# I2C_MUX.net
KiCad netlist of a schematic drawn in Altium Designer
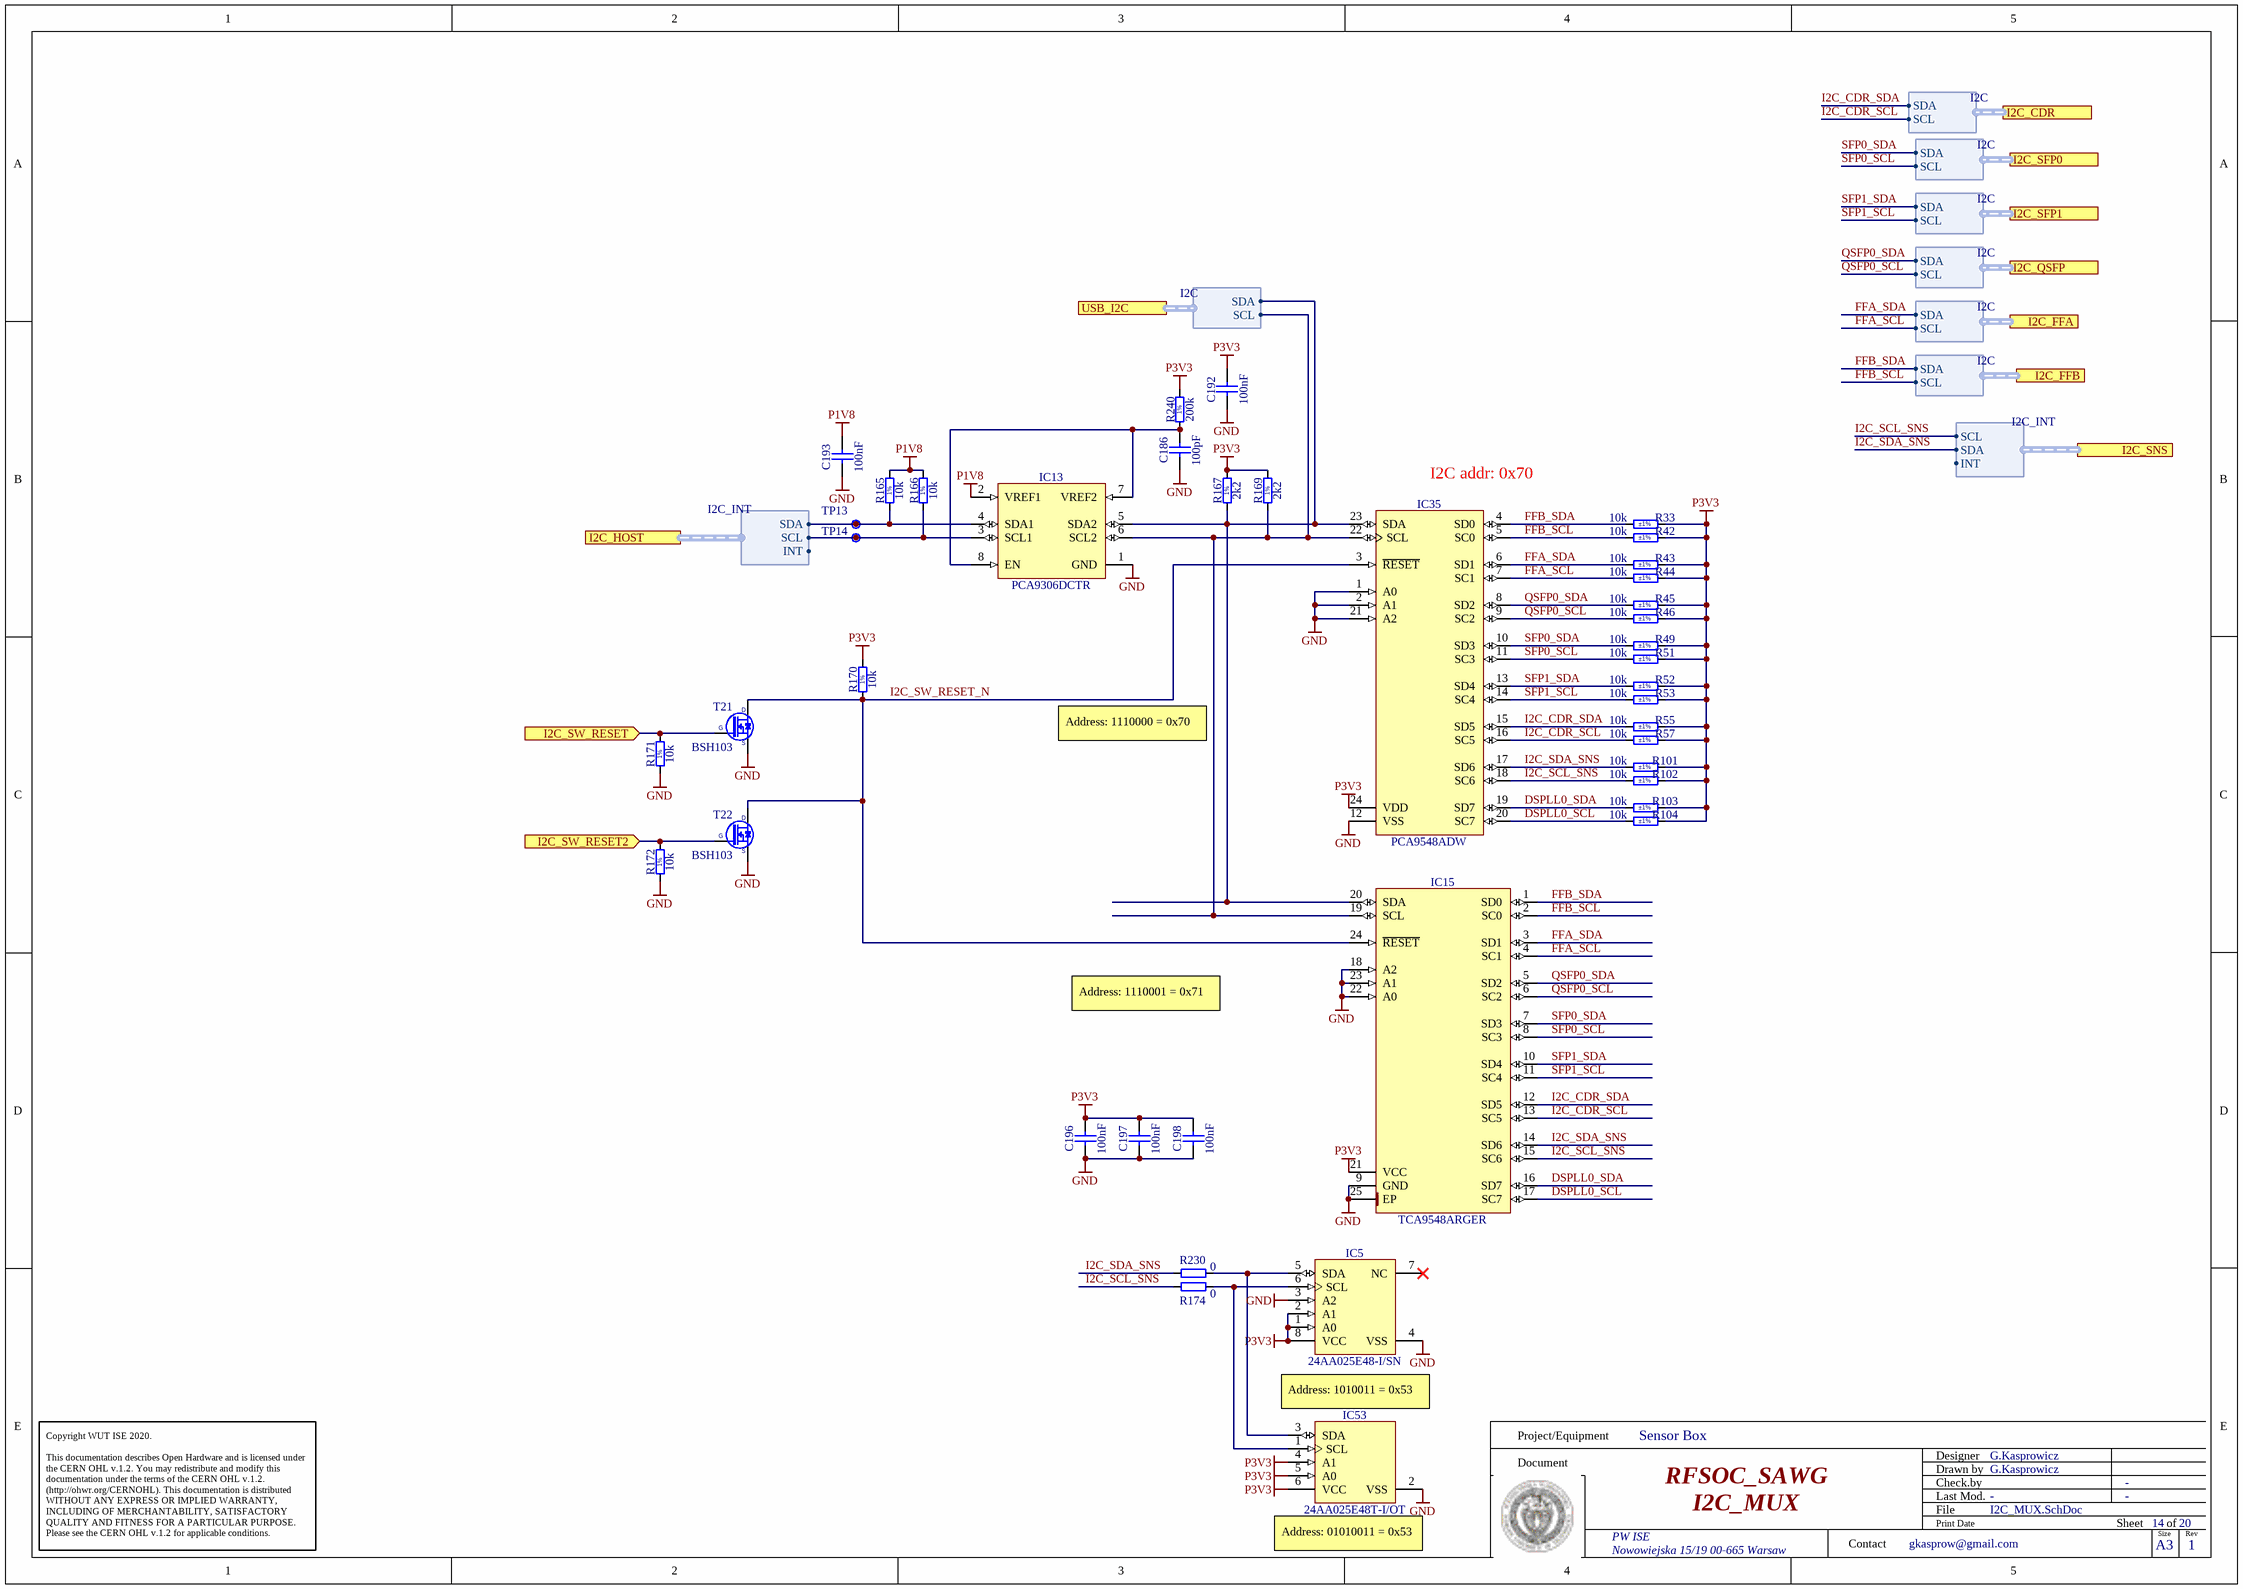
[diagram p0: I2C_MUX.SchDoc]

(export (version "E")
  (design (tool "Eeschema 10.0.6"))
  (components
    (comp (ref "C186")
      (value "100pF")
      (footprint "CAPC1005X55N")
      (description "Non-polarised capacitor")
      (fields
        (field (name "PART NUMBER") "CC0402_100PF_50V_5%_C0G")
        (field (name "VOLTAGE") "50V")
        (field (name "AUTHOR") "CERN DEM JLC")
      )
      (libsource (lib "Capacitors") (part "Capacitor - non polarized"))
    )
    (comp (ref "C192")
      (value "100nF")
      (footprint "CAPC1005X55N")
      (description "Non-polarised capacitor")
      (fields
        (field (name "PART NUMBER") "CC0402_100NF_16V_10%_X7R")
        (field (name "VOLTAGE") "16V")
        (field (name "AUTHOR") "CERN DEM JLC")
      )
      (libsource (lib "Capacitors") (part "Capacitor - non polarized"))
    )
    (comp (ref "C193")
      (value "100nF")
      (footprint "CAPC1005X55N")
      (description "Non-polarised capacitor")
      (fields
        (field (name "PART NUMBER") "CC0402_100NF_16V_10%_X7R")
        (field (name "VOLTAGE") "16V")
        (field (name "AUTHOR") "CERN DEM JLC")
      )
      (libsource (lib "Capacitors") (part "Capacitor - non polarized"))
    )
    (comp (ref "C196")
      (value "100nF")
      (footprint "CAPC1005X55N")
      (description "Non-polarised capacitor")
      (fields
        (field (name "PART NUMBER") "CC0402_100NF_16V_10%_X7R")
        (field (name "VOLTAGE") "16V")
        (field (name "AUTHOR") "CERN DEM JLC")
      )
      (libsource (lib "Capacitors") (part "Capacitor - non polarized"))
    )
    (comp (ref "C197")
      (value "100nF")
      (footprint "CAPC1005X55N")
      (description "Non-polarised capacitor")
      (fields
        (field (name "PART NUMBER") "CC0402_100NF_16V_10%_X7R")
        (field (name "VOLTAGE") "16V")
        (field (name "AUTHOR") "CERN DEM JLC")
      )
      (libsource (lib "Capacitors") (part "Capacitor - non polarized"))
    )
    (comp (ref "C198")
      (value "100nF")
      (footprint "CAPC1005X55N")
      (description "Non-polarised capacitor")
      (fields
        (field (name "PART NUMBER") "CC0402_100NF_16V_10%_X7R")
        (field (name "VOLTAGE") "16V")
        (field (name "AUTHOR") "CERN DEM JLC")
      )
      (libsource (lib "Capacitors") (part "Capacitor - non polarized"))
    )
    (comp (ref "IC5")
      (value "24AA025E48-I/SN")
      (footprint "SOIC127P600X175-8N")
      (description "1.7V-5.5V, 2K I2C™ Serial EEPROMs with EUI-48™ Node Identity")
      (fields (field (name "MANUFACTURER") "MICROCHIP TECHNOLOGY") (field (name "AUTHOR") "CERN DEM MR"))
      (libsource (lib "ICs And Semiconductors") (part "24AA025E48-I/SN"))
    )
    (comp (ref "IC13")
      (value "PCA9306DCTR")
      (footprint "SOP65P400X130-8N")
      (description "Dual Bidirectional I2C Bus And SMBus Voltage-Level Translator")
      (fields (field (name "MANUFACTURER") "TEXAS INSTRUMENTS") (field (name "AUTHOR") "CERN DEM JLC"))
      (libsource (lib "ICs And Semiconductors") (part "PCA9306D"))
    )
    (comp (ref "IC15")
      (value "TCA9548ARGER")
      (footprint "QFN50P400X400X100-25N-S220")
      (description "Low Voltage 8-Channel I2C Switch With Reset")
      (fields (field (name "MANUFACTURER") "TEXAS INSTRUMENTS") (field (name "AUTHOR") "CERN DEM JLC"))
      (libsource (lib "ICs And Semiconductors") (part "TCA9548ARGER"))
    )
    (comp (ref "IC35")
      (value "PCA9548ADW")
      (footprint "SOIC127P1030X265-24N")
      (description "8-Channel I2C-Bus Switch with Reset")
      (fields (field (name "MANUFACTURER") "TEXAS INSTRUMENTS") (field (name "AUTHOR") "CERN DEM JLC"))
      (libsource (lib "ICs And Semiconductors") (part "PCA9548ADW"))
    )
    (comp (ref "IC53")
      (value "24AA025E48T-I/OT")
      (footprint "SOT95P280X145-6N")
      (description "1.7V-5.5V, 2K I2C Serial EEPROM With EUI-48 Node Identity")
      (fields (field (name "MANUFACTURER") "MICROCHIP TECHNOLOGY") (field (name "AUTHOR") "CERN DEM BC"))
      (libsource (lib "ICs And Semiconductors") (part "24AA025E48T-I/OT"))
    )
    (comp (ref "R33")
      (value "10k")
      (footprint "RESC1005X40N")
      (description "Resistor - 1%")
      (fields
        (field (name "TOLERANCE") "±1%")
        (field (name "PART NUMBER") "R0402_10K_1%_0.0625W_100PPM")
        (field (name "POWER") "0.0625W")
        (field (name "AUTHOR") "CERN DEM JLC")
      )
      (libsource (lib "Resistors") (part "Resistor - 1%"))
    )
    (comp (ref "R42")
      (value "10k")
      (footprint "RESC1005X40N")
      (description "Resistor - 1%")
      (fields
        (field (name "TOLERANCE") "±1%")
        (field (name "PART NUMBER") "R0402_10K_1%_0.0625W_100PPM")
        (field (name "POWER") "0.0625W")
        (field (name "AUTHOR") "CERN DEM JLC")
      )
      (libsource (lib "Resistors") (part "Resistor - 1%"))
    )
    (comp (ref "R43")
      (value "10k")
      (footprint "RESC1005X40N")
      (description "Resistor - 1%")
      (fields
        (field (name "TOLERANCE") "±1%")
        (field (name "PART NUMBER") "R0402_10K_1%_0.0625W_100PPM")
        (field (name "POWER") "0.0625W")
        (field (name "AUTHOR") "CERN DEM JLC")
      )
      (libsource (lib "Resistors") (part "Resistor - 1%"))
    )
    (comp (ref "R44")
      (value "10k")
      (footprint "RESC1005X40N")
      (description "Resistor - 1%")
      (fields
        (field (name "TOLERANCE") "±1%")
        (field (name "PART NUMBER") "R0402_10K_1%_0.0625W_100PPM")
        (field (name "POWER") "0.0625W")
        (field (name "AUTHOR") "CERN DEM JLC")
      )
      (libsource (lib "Resistors") (part "Resistor - 1%"))
    )
    (comp (ref "R45")
      (value "10k")
      (footprint "RESC1005X40N")
      (description "Resistor - 1%")
      (fields
        (field (name "TOLERANCE") "±1%")
        (field (name "PART NUMBER") "R0402_10K_1%_0.0625W_100PPM")
        (field (name "POWER") "0.0625W")
        (field (name "AUTHOR") "CERN DEM JLC")
      )
      (libsource (lib "Resistors") (part "Resistor - 1%"))
    )
    (comp (ref "R46")
      (value "10k")
      (footprint "RESC1005X40N")
      (description "Resistor - 1%")
      (fields
        (field (name "TOLERANCE") "±1%")
        (field (name "PART NUMBER") "R0402_10K_1%_0.0625W_100PPM")
        (field (name "POWER") "0.0625W")
        (field (name "AUTHOR") "CERN DEM JLC")
      )
      (libsource (lib "Resistors") (part "Resistor - 1%"))
    )
    (comp (ref "R49")
      (value "10k")
      (footprint "RESC1005X40N")
      (description "Resistor - 1%")
      (fields
        (field (name "TOLERANCE") "±1%")
        (field (name "PART NUMBER") "R0402_10K_1%_0.0625W_100PPM")
        (field (name "POWER") "0.0625W")
        (field (name "AUTHOR") "CERN DEM JLC")
      )
      (libsource (lib "Resistors") (part "Resistor - 1%"))
    )
    (comp (ref "R51")
      (value "10k")
      (footprint "RESC1005X40N")
      (description "Resistor - 1%")
      (fields
        (field (name "TOLERANCE") "±1%")
        (field (name "PART NUMBER") "R0402_10K_1%_0.0625W_100PPM")
        (field (name "POWER") "0.0625W")
        (field (name "AUTHOR") "CERN DEM JLC")
      )
      (libsource (lib "Resistors") (part "Resistor - 1%"))
    )
    (comp (ref "R52")
      (value "10k")
      (footprint "RESC1005X40N")
      (description "Resistor - 1%")
      (fields
        (field (name "TOLERANCE") "±1%")
        (field (name "PART NUMBER") "R0402_10K_1%_0.0625W_100PPM")
        (field (name "POWER") "0.0625W")
        (field (name "AUTHOR") "CERN DEM JLC")
      )
      (libsource (lib "Resistors") (part "Resistor - 1%"))
    )
    (comp (ref "R53")
      (value "10k")
      (footprint "RESC1005X40N")
      (description "Resistor - 1%")
      (fields
        (field (name "TOLERANCE") "±1%")
        (field (name "PART NUMBER") "R0402_10K_1%_0.0625W_100PPM")
        (field (name "POWER") "0.0625W")
        (field (name "AUTHOR") "CERN DEM JLC")
      )
      (libsource (lib "Resistors") (part "Resistor - 1%"))
    )
    (comp (ref "R55")
      (value "10k")
      (footprint "RESC1005X40N")
      (description "Resistor - 1%")
      (fields
        (field (name "TOLERANCE") "±1%")
        (field (name "PART NUMBER") "R0402_10K_1%_0.0625W_100PPM")
        (field (name "POWER") "0.0625W")
        (field (name "AUTHOR") "CERN DEM JLC")
      )
      (libsource (lib "Resistors") (part "Resistor - 1%"))
    )
    (comp (ref "R57")
      (value "10k")
      (footprint "RESC1005X40N")
      (description "Resistor - 1%")
      (fields
        (field (name "TOLERANCE") "±1%")
        (field (name "PART NUMBER") "R0402_10K_1%_0.0625W_100PPM")
        (field (name "POWER") "0.0625W")
        (field (name "AUTHOR") "CERN DEM JLC")
      )
      (libsource (lib "Resistors") (part "Resistor - 1%"))
    )
    (comp (ref "R101")
      (value "10k")
      (footprint "RESC1005X40N")
      (description "Resistor - 1%")
      (fields
        (field (name "TOLERANCE") "±1%")
        (field (name "PART NUMBER") "R0402_10K_1%_0.0625W_100PPM")
        (field (name "POWER") "0.0625W")
        (field (name "AUTHOR") "CERN DEM JLC")
      )
      (libsource (lib "Resistors") (part "Resistor - 1%"))
    )
    (comp (ref "R102")
      (value "10k")
      (footprint "RESC1005X40N")
      (description "Resistor - 1%")
      (fields
        (field (name "TOLERANCE") "±1%")
        (field (name "PART NUMBER") "R0402_10K_1%_0.0625W_100PPM")
        (field (name "POWER") "0.0625W")
        (field (name "AUTHOR") "CERN DEM JLC")
      )
      (libsource (lib "Resistors") (part "Resistor - 1%"))
    )
    (comp (ref "R103")
      (value "10k")
      (footprint "RESC1005X40N")
      (description "Resistor - 1%")
      (fields
        (field (name "TOLERANCE") "±1%")
        (field (name "PART NUMBER") "R0402_10K_1%_0.0625W_100PPM")
        (field (name "POWER") "0.0625W")
        (field (name "AUTHOR") "CERN DEM JLC")
      )
      (libsource (lib "Resistors") (part "Resistor - 1%"))
    )
    (comp (ref "R104")
      (value "10k")
      (footprint "RESC1005X40N")
      (description "Resistor - 1%")
      (fields
        (field (name "TOLERANCE") "±1%")
        (field (name "PART NUMBER") "R0402_10K_1%_0.0625W_100PPM")
        (field (name "POWER") "0.0625W")
        (field (name "AUTHOR") "CERN DEM JLC")
      )
      (libsource (lib "Resistors") (part "Resistor - 1%"))
    )
    (comp (ref "R165")
      (value "10k")
      (footprint "RESC1005X40N")
      (description "Resistor - 1%")
      (fields
        (field (name "PART NUMBER") "R0402_10K_1%_0.0625W_100PPM")
        (field (name "POWER") "0.0625W")
        (field (name "AUTHOR") "CERN DEM JLC")
      )
      (libsource (lib "Resistors") (part "Resistor - 1%"))
    )
    (comp (ref "R166")
      (value "10k")
      (footprint "RESC1005X40N")
      (description "Resistor - 1%")
      (fields
        (field (name "PART NUMBER") "R0402_10K_1%_0.0625W_100PPM")
        (field (name "POWER") "0.0625W")
        (field (name "AUTHOR") "CERN DEM JLC")
      )
      (libsource (lib "Resistors") (part "Resistor - 1%"))
    )
    (comp (ref "R167")
      (value "2k2")
      (footprint "RESC1005X40N")
      (description "Resistor - 1%")
      (fields
        (field (name "PART NUMBER") "R0402_2K2_1%_0.0625W_100PPM")
        (field (name "POWER") "0.0625W")
        (field (name "AUTHOR") "CERN DEM JLC")
      )
      (libsource (lib "Resistors") (part "Resistor - 1%"))
    )
    (comp (ref "R169")
      (value "2k2")
      (footprint "RESC1005X40N")
      (description "Resistor - 1%")
      (fields
        (field (name "PART NUMBER") "R0402_2K2_1%_0.0625W_100PPM")
        (field (name "POWER") "0.0625W")
        (field (name "AUTHOR") "CERN DEM JLC")
      )
      (libsource (lib "Resistors") (part "Resistor - 1%"))
    )
    (comp (ref "R170")
      (value "10k")
      (footprint "RESC1005X40N")
      (description "Resistor - 1%")
      (fields
        (field (name "PART NUMBER") "R0402_10K_1%_0.0625W_100PPM")
        (field (name "POWER") "0.0625W")
        (field (name "AUTHOR") "CERN DEM JLC")
      )
      (libsource (lib "Resistors") (part "Resistor - 1%"))
    )
    (comp (ref "R171")
      (value "10k")
      (footprint "RESC1005X40N")
      (description "Resistor - 1%")
      (fields
        (field (name "PART NUMBER") "R0402_10K_1%_0.0625W_100PPM")
        (field (name "POWER") "0.0625W")
        (field (name "AUTHOR") "CERN DEM JLC")
      )
      (libsource (lib "Resistors") (part "Resistor - 1%"))
    )
    (comp (ref "R172")
      (value "10k")
      (footprint "RESC1005X40N")
      (description "Resistor - 1%")
      (fields
        (field (name "PART NUMBER") "R0402_10K_1%_0.0625W_100PPM")
        (field (name "POWER") "0.0625W")
        (field (name "AUTHOR") "CERN DEM JLC")
      )
      (libsource (lib "Resistors") (part "Resistor - 1%"))
    )
    (comp (ref "R174")
      (value "0")
      (footprint "RESC1005X40N")
      (description "Resistor")
      (fields
        (field (name "PART NUMBER") "R0402_0R_JUMPER")
        (field (name "MANUFACTURER") "GENERIC")
        (field (name "AUTHOR") "CERN DEM JLC")
      )
      (libsource (lib "Resistors") (part "Resistor"))
    )
    (comp (ref "R230")
      (value "0")
      (footprint "RESC1005X40N")
      (description "Resistor")
      (fields
        (field (name "PART NUMBER") "R0402_0R_JUMPER")
        (field (name "MANUFACTURER") "GENERIC")
        (field (name "AUTHOR") "CERN DEM JLC")
      )
      (libsource (lib "Resistors") (part "Resistor"))
    )
    (comp (ref "R240")
      (value "200k")
      (footprint "RESC1005X40N")
      (description "Resistor - 1%")
      (fields
        (field (name "PART NUMBER") "R0402_200K_1%_0.0625W_100PPM")
        (field (name "POWER") "0.0625W")
        (field (name "AUTHOR") "CERN DEM JLC")
      )
      (libsource (lib "Resistors") (part "Resistor - 1%"))
    )
    (comp (ref "T21")
      (value "BSH103")
      (footprint "SOT95P230X110-3N")
      (description "N-CHANNEL MOSFET WITH DIODE")
      (fields (field (name "MANUFACTURER") "NEXPERIA") (field (name "AUTHOR") "CERN DEM JLC"))
      (libsource (lib "ICs And Semiconductors") (part "N-MOSFET-D 1G 2S 3D"))
    )
    (comp (ref "T22")
      (value "BSH103")
      (footprint "SOT95P230X110-3N")
      (description "N-CHANNEL MOSFET WITH DIODE")
      (fields (field (name "MANUFACTURER") "NEXPERIA") (field (name "AUTHOR") "CERN DEM JLC"))
      (libsource (lib "ICs And Semiconductors") (part "N-MOSFET-D 1G 2S 3D"))
    )
    (comp (ref "TP13")
      (value "Test Point")
      (footprint "TPS127")
      (fields (field (name "PART NUMBER") "SMD_PAD_1.27X1.27MM") (field (name "AUTHOR") "CERN DEM JLC"))
      (libsource (lib "Eletro-mechanical") (part "Test Point"))
    )
    (comp (ref "TP14")
      (value "Test Point")
      (footprint "TPS127")
      (fields (field (name "PART NUMBER") "SMD_PAD_1.27X1.27MM") (field (name "AUTHOR") "CERN DEM JLC"))
      (libsource (lib "Eletro-mechanical") (part "Test Point"))
    )
  )
  (nets
    (net (code "3") (name "/DSPLL0_SCL") (class "Default")
      (node (ref "IC15") (pin "17") (pinfunction "SC7_17") (pintype "bidirectional"))
      (node (ref "IC35") (pin "20") (pinfunction "SC7_20") (pintype "bidirectional"))
      (node (ref "R104") (pin "1") (pinfunction "1_1") (pintype "passive"))
    )
    (net (code "4") (name "/DSPLL0_SDA") (class "Default")
      (node (ref "IC15") (pin "16") (pinfunction "SD7_16") (pintype "bidirectional"))
      (node (ref "IC35") (pin "19") (pinfunction "SD7_19") (pintype "bidirectional"))
      (node (ref "R103") (pin "1") (pinfunction "1_1") (pintype "passive"))
    )
    (net (code "5") (name "/FFA_SCL") (class "Default")
      (node (ref "IC15") (pin "4") (pinfunction "SC1_4") (pintype "bidirectional"))
      (node (ref "IC35") (pin "7") (pinfunction "SC1_7") (pintype "bidirectional"))
      (node (ref "R44") (pin "1") (pinfunction "1_1") (pintype "passive"))
    )
    (net (code "6") (name "/FFA_SDA") (class "Default")
      (node (ref "IC15") (pin "3") (pinfunction "SD1_3") (pintype "bidirectional"))
      (node (ref "IC35") (pin "6") (pinfunction "SD1_6") (pintype "bidirectional"))
      (node (ref "R43") (pin "1") (pinfunction "1_1") (pintype "passive"))
    )
    (net (code "7") (name "/FFB_SCL") (class "Default")
      (node (ref "IC15") (pin "2") (pinfunction "SC0_2") (pintype "bidirectional"))
      (node (ref "IC35") (pin "5") (pinfunction "SC0_5") (pintype "bidirectional"))
      (node (ref "R42") (pin "1") (pinfunction "1_1") (pintype "passive"))
    )
    (net (code "8") (name "/FFB_SDA") (class "Default")
      (node (ref "IC15") (pin "1") (pinfunction "SD0_1") (pintype "bidirectional"))
      (node (ref "IC35") (pin "4") (pinfunction "SD0_4") (pintype "bidirectional"))
      (node (ref "R33") (pin "1") (pinfunction "1_1") (pintype "passive"))
    )
    (net (code "9") (name "/I2C_CDR_SCL") (class "Default")
      (node (ref "IC15") (pin "13") (pinfunction "SC5_13") (pintype "bidirectional"))
      (node (ref "IC35") (pin "16") (pinfunction "SC5_16") (pintype "bidirectional"))
      (node (ref "R57") (pin "1") (pinfunction "1_1") (pintype "passive"))
    )
    (net (code "10") (name "/I2C_CDR_SDA") (class "Default")
      (node (ref "IC15") (pin "12") (pinfunction "SD5_12") (pintype "bidirectional"))
      (node (ref "IC35") (pin "15") (pinfunction "SD5_15") (pintype "bidirectional"))
      (node (ref "R55") (pin "1") (pinfunction "1_1") (pintype "passive"))
    )
    (net (code "11") (name "/I2C_SCL_SNS") (class "Default")
      (node (ref "IC15") (pin "15") (pinfunction "SC6_15") (pintype "bidirectional"))
      (node (ref "IC35") (pin "18") (pinfunction "SC6_18") (pintype "bidirectional"))
      (node (ref "R102") (pin "1") (pinfunction "1_1") (pintype "passive"))
      (node (ref "R174") (pin "1") (pinfunction "1_1") (pintype "passive"))
    )
    (net (code "12") (name "/I2C_SDA_SNS") (class "Default")
      (node (ref "IC15") (pin "14") (pinfunction "SD6_14") (pintype "bidirectional"))
      (node (ref "IC35") (pin "17") (pinfunction "SD6_17") (pintype "bidirectional"))
      (node (ref "R101") (pin "1") (pinfunction "1_1") (pintype "passive"))
      (node (ref "R230") (pin "1") (pinfunction "1_1") (pintype "passive"))
    )
    (net (code "13") (name "/I2C_SW_RESET") (class "Default")
      (node (ref "R171") (pin "2") (pinfunction "2_2") (pintype "passive"))
      (node (ref "T21") (pin "1") (pinfunction "G_1") (pintype "passive"))
    )
    (net (code "14") (name "/I2C_SW_RESET2") (class "Default")
      (node (ref "R172") (pin "2") (pinfunction "2_2") (pintype "passive"))
      (node (ref "T22") (pin "1") (pinfunction "G_1") (pintype "passive"))
    )
    (net (code "15") (name "/I2C_SW_RESET_N") (class "Default")
      (node (ref "IC15") (pin "24") (pinfunction "~{RESET}_24") (pintype "input"))
      (node (ref "IC35") (pin "3") (pinfunction "~{RESET}_3") (pintype "input"))
      (node (ref "R170") (pin "1") (pinfunction "1_1") (pintype "passive"))
      (node (ref "T21") (pin "3") (pinfunction "D_3") (pintype "passive"))
      (node (ref "T22") (pin "3") (pinfunction "D_3") (pintype "passive"))
    )
    (net (code "16") (name "/QSFP0_SCL") (class "Default")
      (node (ref "IC15") (pin "6") (pinfunction "SC2_6") (pintype "bidirectional"))
      (node (ref "IC35") (pin "9") (pinfunction "SC2_9") (pintype "bidirectional"))
      (node (ref "R46") (pin "1") (pinfunction "1_1") (pintype "passive"))
    )
    (net (code "17") (name "/QSFP0_SDA") (class "Default")
      (node (ref "IC15") (pin "5") (pinfunction "SD2_5") (pintype "bidirectional"))
      (node (ref "IC35") (pin "8") (pinfunction "SD2_8") (pintype "bidirectional"))
      (node (ref "R45") (pin "1") (pinfunction "1_1") (pintype "passive"))
    )
    (net (code "18") (name "/SFP0_SCL") (class "Default")
      (node (ref "IC15") (pin "8") (pinfunction "SC3_8") (pintype "bidirectional"))
      (node (ref "IC35") (pin "11") (pinfunction "SC3_11") (pintype "bidirectional"))
      (node (ref "R51") (pin "1") (pinfunction "1_1") (pintype "passive"))
    )
    (net (code "19") (name "/SFP0_SDA") (class "Default")
      (node (ref "IC15") (pin "7") (pinfunction "SD3_7") (pintype "bidirectional"))
      (node (ref "IC35") (pin "10") (pinfunction "SD3_10") (pintype "bidirectional"))
      (node (ref "R49") (pin "1") (pinfunction "1_1") (pintype "passive"))
    )
    (net (code "20") (name "/SFP1_SCL") (class "Default")
      (node (ref "IC15") (pin "11") (pinfunction "SC4_11") (pintype "bidirectional"))
      (node (ref "IC35") (pin "14") (pinfunction "SC4_14") (pintype "bidirectional"))
      (node (ref "R53") (pin "1") (pinfunction "1_1") (pintype "passive"))
    )
    (net (code "21") (name "/SFP1_SDA") (class "Default")
      (node (ref "IC15") (pin "10") (pinfunction "SD4_10") (pintype "bidirectional"))
      (node (ref "IC35") (pin "13") (pinfunction "SD4_13") (pintype "bidirectional"))
      (node (ref "R52") (pin "1") (pinfunction "1_1") (pintype "passive"))
    )
    (net (code "24") (name "GND") (class "Default")
      (node (ref "C186") (pin "1") (pinfunction "1_1") (pintype "passive"))
      (node (ref "C192") (pin "1") (pinfunction "1_1") (pintype "passive"))
      (node (ref "C193") (pin "1") (pinfunction "1_1") (pintype "passive"))
      (node (ref "C196") (pin "1") (pinfunction "1_1") (pintype "passive"))
      (node (ref "C197") (pin "1") (pinfunction "1_1") (pintype "passive"))
      (node (ref "C198") (pin "1") (pinfunction "1_1") (pintype "passive"))
      (node (ref "IC13") (pin "1") (pinfunction "GND_1") (pintype "power_in"))
      (node (ref "IC15") (pin "18") (pinfunction "A2_18") (pintype "input"))
      (node (ref "IC15") (pin "22") (pinfunction "A0_22") (pintype "input"))
      (node (ref "IC15") (pin "23") (pinfunction "A1_23") (pintype "input"))
      (node (ref "IC15") (pin "25") (pinfunction "EP_25") (pintype "power_in"))
      (node (ref "IC15") (pin "9") (pinfunction "GND_9") (pintype "power_in"))
      (node (ref "IC35") (pin "1") (pinfunction "A0_1") (pintype "input"))
      (node (ref "IC35") (pin "12") (pinfunction "VSS_12") (pintype "power_in"))
      (node (ref "IC35") (pin "2") (pinfunction "A1_2") (pintype "input"))
      (node (ref "IC35") (pin "21") (pinfunction "A2_21") (pintype "input"))
      (node (ref "IC5") (pin "3") (pinfunction "A2_3") (pintype "input"))
      (node (ref "IC5") (pin "4") (pinfunction "VSS_4") (pintype "power_in"))
      (node (ref "IC53") (pin "2") (pinfunction "VSS_2") (pintype "power_in"))
      (node (ref "R171") (pin "1") (pinfunction "1_1") (pintype "passive"))
      (node (ref "R172") (pin "1") (pinfunction "1_1") (pintype "passive"))
      (node (ref "T21") (pin "2") (pinfunction "S_2") (pintype "passive"))
      (node (ref "T22") (pin "2") (pinfunction "S_2") (pintype "passive"))
    )
    (net (code "25") (name "Net-(IC5-SCL)") (class "Default")
      (node (ref "IC5") (pin "6") (pinfunction "SCL_6") (pintype "input"))
      (node (ref "IC53") (pin "1") (pinfunction "SCL_1") (pintype "input"))
      (node (ref "R174") (pin "2") (pinfunction "2_2") (pintype "passive"))
    )
    (net (code "26") (name "Net-(IC5-SDA)") (class "Default")
      (node (ref "IC5") (pin "5") (pinfunction "SDA_5") (pintype "bidirectional"))
      (node (ref "IC53") (pin "3") (pinfunction "SDA_3") (pintype "bidirectional"))
      (node (ref "R230") (pin "2") (pinfunction "2_2") (pintype "passive"))
    )
    (net (code "27") (name "Net-(IC13-EN)") (class "Default")
      (node (ref "C186") (pin "2") (pinfunction "2_2") (pintype "passive"))
      (node (ref "IC13") (pin "7") (pinfunction "VREF2_7") (pintype "input"))
      (node (ref "IC13") (pin "8") (pinfunction "EN_8") (pintype "input"))
      (node (ref "R240") (pin "1") (pinfunction "1_1") (pintype "passive"))
    )
    (net (code "28") (name "Net-(IC13-SCL1)") (class "Default")
      (node (ref "IC13") (pin "3") (pinfunction "SCL1_3") (pintype "bidirectional"))
      (node (ref "R166") (pin "1") (pinfunction "1_1") (pintype "passive"))
      (node (ref "TP14") (pin "1") (pinfunction "1_1") (pintype "bidirectional"))
    )
    (net (code "29") (name "Net-(IC13-SCL2)") (class "Default")
      (node (ref "IC13") (pin "6") (pinfunction "SCL2_6") (pintype "bidirectional"))
      (node (ref "IC15") (pin "19") (pinfunction "SCL_19") (pintype "bidirectional"))
      (node (ref "IC35") (pin "22") (pinfunction "SCL_22") (pintype "bidirectional"))
      (node (ref "R169") (pin "1") (pinfunction "1_1") (pintype "passive"))
    )
    (net (code "30") (name "Net-(IC13-SDA1)") (class "Default")
      (node (ref "IC13") (pin "4") (pinfunction "SDA1_4") (pintype "bidirectional"))
      (node (ref "R165") (pin "1") (pinfunction "1_1") (pintype "passive"))
      (node (ref "TP13") (pin "1") (pinfunction "1_1") (pintype "bidirectional"))
    )
    (net (code "31") (name "Net-(IC13-SDA2)") (class "Default")
      (node (ref "IC13") (pin "5") (pinfunction "SDA2_5") (pintype "bidirectional"))
      (node (ref "IC15") (pin "20") (pinfunction "SDA_20") (pintype "bidirectional"))
      (node (ref "IC35") (pin "23") (pinfunction "SDA_23") (pintype "bidirectional"))
      (node (ref "R167") (pin "1") (pinfunction "1_1") (pintype "passive"))
    )
    (net (code "32") (name "P1V8") (class "Default")
      (node (ref "C193") (pin "2") (pinfunction "2_2") (pintype "passive"))
      (node (ref "IC13") (pin "2") (pinfunction "VREF1_2") (pintype "input"))
      (node (ref "R165") (pin "2") (pinfunction "2_2") (pintype "passive"))
      (node (ref "R166") (pin "2") (pinfunction "2_2") (pintype "passive"))
    )
    (net (code "33") (name "P3V3") (class "Default")
      (node (ref "C192") (pin "2") (pinfunction "2_2") (pintype "passive"))
      (node (ref "C196") (pin "2") (pinfunction "2_2") (pintype "passive"))
      (node (ref "C197") (pin "2") (pinfunction "2_2") (pintype "passive"))
      (node (ref "C198") (pin "2") (pinfunction "2_2") (pintype "passive"))
      (node (ref "IC15") (pin "21") (pinfunction "VCC_21") (pintype "power_in"))
      (node (ref "IC35") (pin "24") (pinfunction "VDD_24") (pintype "power_in"))
      (node (ref "IC5") (pin "1") (pinfunction "A0_1") (pintype "input"))
      (node (ref "IC5") (pin "2") (pinfunction "A1_2") (pintype "input"))
      (node (ref "IC5") (pin "8") (pinfunction "VCC_8") (pintype "power_in"))
      (node (ref "IC53") (pin "4") (pinfunction "A1_4") (pintype "input"))
      (node (ref "IC53") (pin "5") (pinfunction "A0_5") (pintype "input"))
      (node (ref "IC53") (pin "6") (pinfunction "VCC_6") (pintype "power_in"))
      (node (ref "R101") (pin "2") (pinfunction "2_2") (pintype "passive"))
      (node (ref "R102") (pin "2") (pinfunction "2_2") (pintype "passive"))
      (node (ref "R103") (pin "2") (pinfunction "2_2") (pintype "passive"))
      (node (ref "R104") (pin "2") (pinfunction "2_2") (pintype "passive"))
      (node (ref "R167") (pin "2") (pinfunction "2_2") (pintype "passive"))
      (node (ref "R169") (pin "2") (pinfunction "2_2") (pintype "passive"))
      (node (ref "R170") (pin "2") (pinfunction "2_2") (pintype "passive"))
      (node (ref "R240") (pin "2") (pinfunction "2_2") (pintype "passive"))
      (node (ref "R33") (pin "2") (pinfunction "2_2") (pintype "passive"))
      (node (ref "R42") (pin "2") (pinfunction "2_2") (pintype "passive"))
      (node (ref "R43") (pin "2") (pinfunction "2_2") (pintype "passive"))
      (node (ref "R44") (pin "2") (pinfunction "2_2") (pintype "passive"))
      (node (ref "R45") (pin "2") (pinfunction "2_2") (pintype "passive"))
      (node (ref "R46") (pin "2") (pinfunction "2_2") (pintype "passive"))
      (node (ref "R49") (pin "2") (pinfunction "2_2") (pintype "passive"))
      (node (ref "R51") (pin "2") (pinfunction "2_2") (pintype "passive"))
      (node (ref "R52") (pin "2") (pinfunction "2_2") (pintype "passive"))
      (node (ref "R53") (pin "2") (pinfunction "2_2") (pintype "passive"))
      (node (ref "R55") (pin "2") (pinfunction "2_2") (pintype "passive"))
      (node (ref "R57") (pin "2") (pinfunction "2_2") (pintype "passive"))
    )
    (net (code "34") (name "unconnected-(IC5-NC-Pad7)") (class "Default")
      (node (ref "IC5") (pin "7") (pinfunction "NC_7") (pintype "passive+no_connect"))
    )
  )
)
